# MachSacXa.net
KiCad netlist of a schematic drawn in Altium Designer
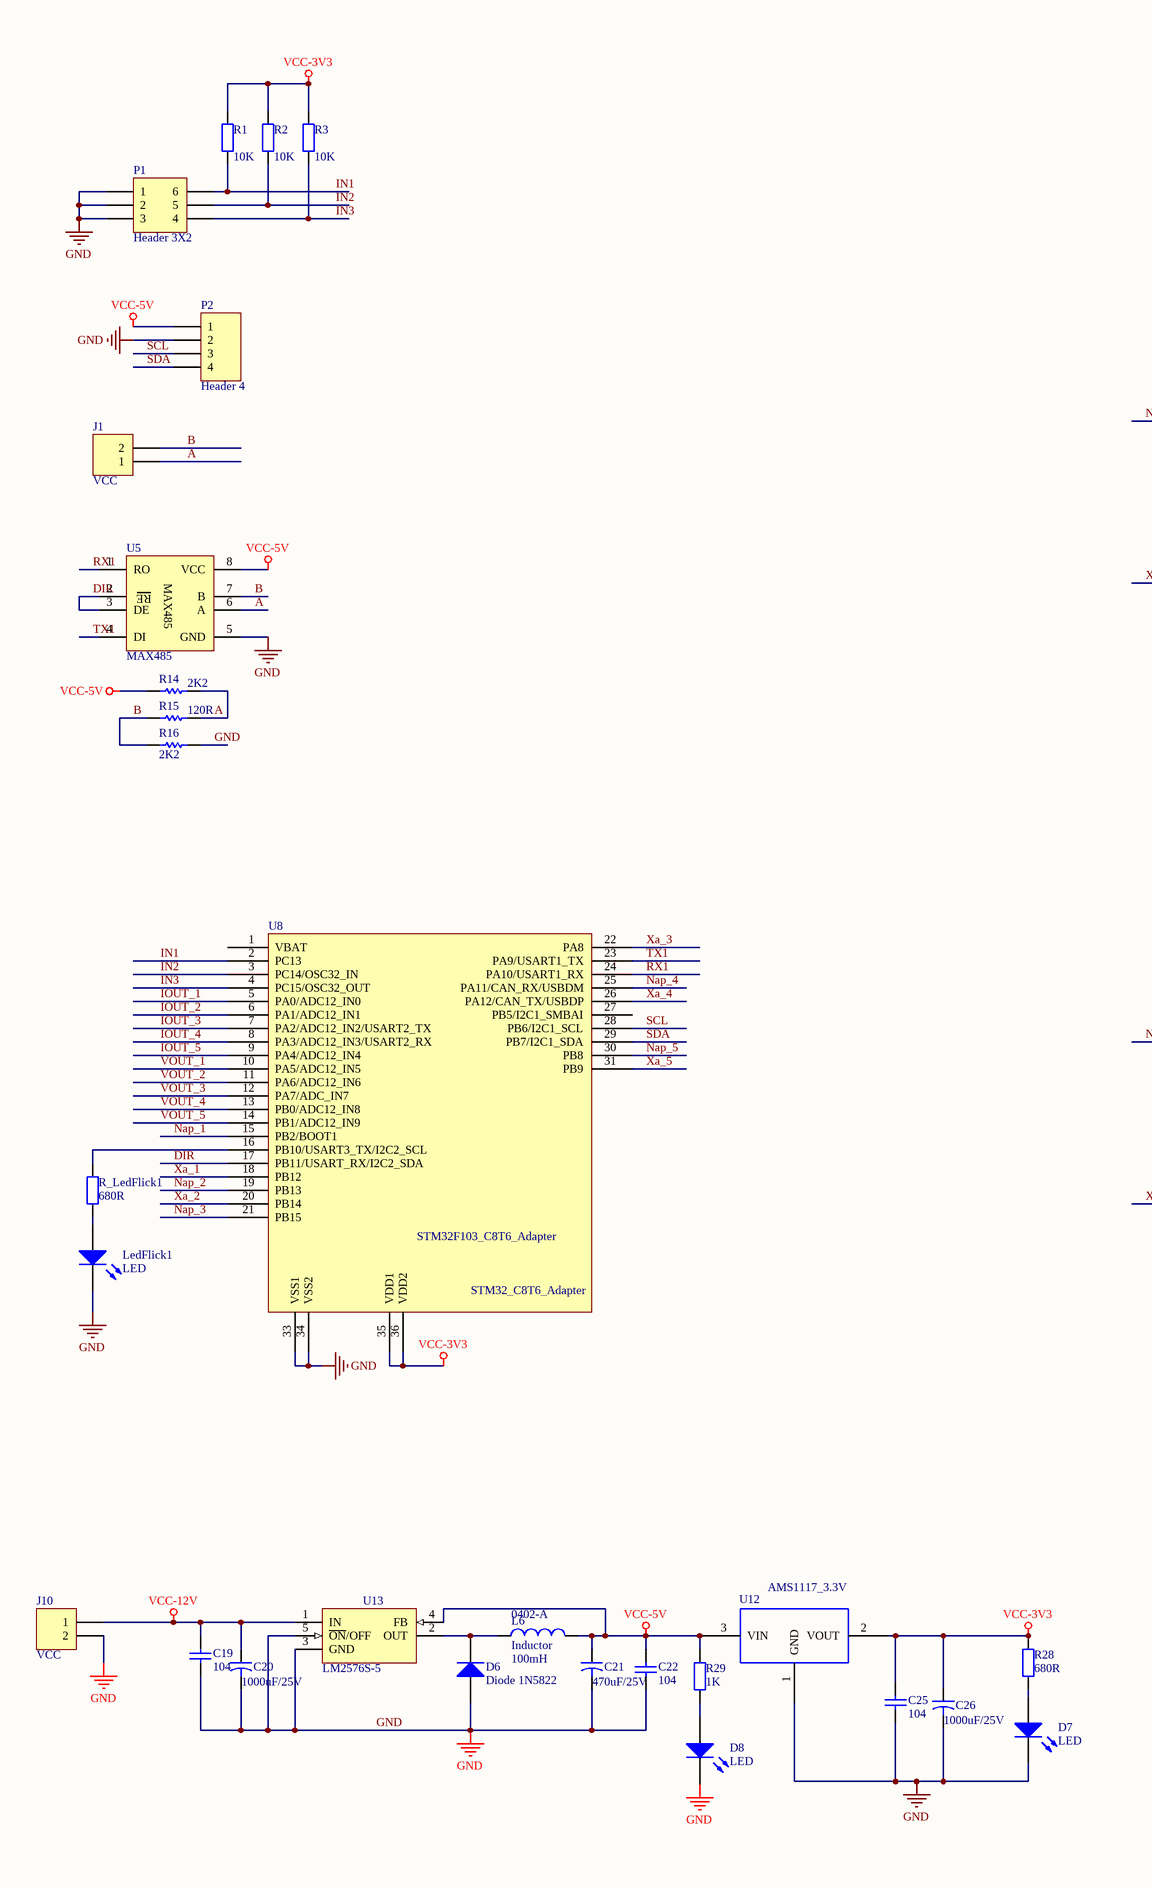
[diagram p0: MachSacXa.SchDoc, left]
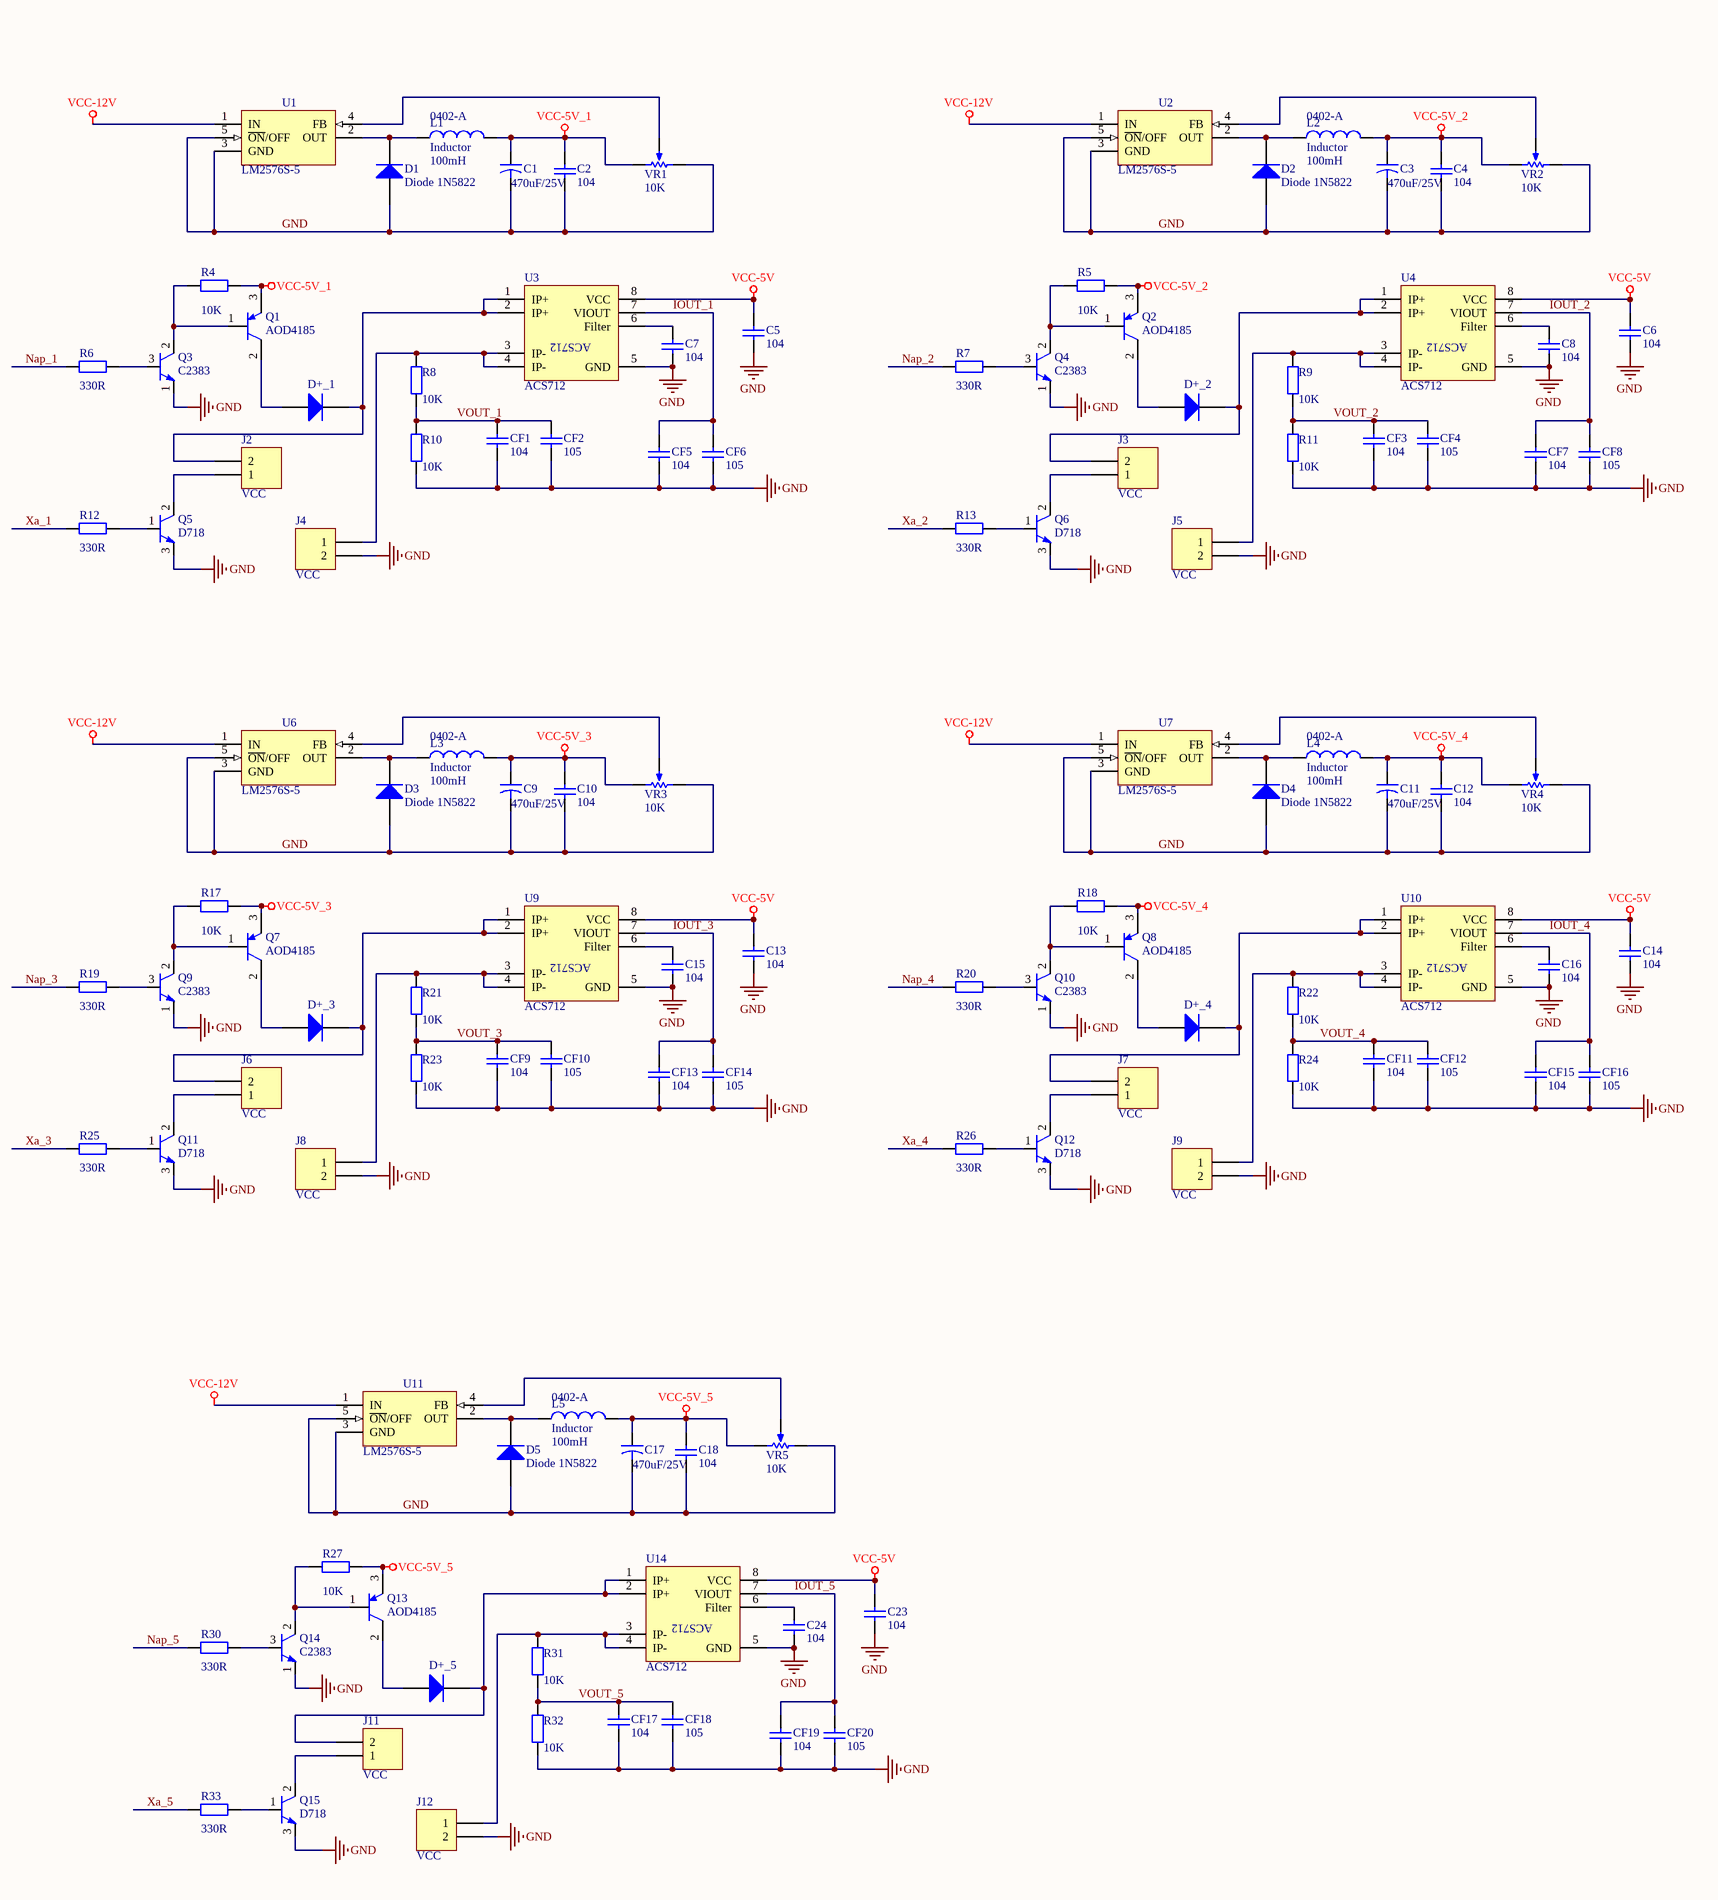
[diagram p1: MachSacXa.SchDoc, right]

(export (version "E")
  (design (tool "Eeschema 10.0.6"))
  (components
    (comp (ref "C1")
      (value "470uF/25V")
      (footprint "C_D300")
      (description "Capacitor")
      (fields (field (name "PUBLISHER") "Altium Limited"))
      (libsource (lib "Miscellaneous Devices") (part "Cap2"))
    )
    (comp (ref "C2")
      (value "104")
      (footprint "IC_dan:R/C_0805")
      (description "Capacitor")
      (fields (field (name "PUBLISHER") "Altium Limited"))
      (libsource (lib "Miscellaneous Devices") (part "Cap"))
    )
    (comp (ref "C3")
      (value "470uF/25V")
      (footprint "C_D300")
      (description "Capacitor")
      (fields (field (name "PUBLISHER") "Altium Limited"))
      (libsource (lib "Miscellaneous Devices") (part "Cap2"))
    )
    (comp (ref "C4")
      (value "104")
      (footprint "IC_dan:R/C_0805")
      (description "Capacitor")
      (fields (field (name "PUBLISHER") "Altium Limited"))
      (libsource (lib "Miscellaneous Devices") (part "Cap"))
    )
    (comp (ref "C5")
      (value "104")
      (footprint "IC_dan:R/C_0805")
      (description "Capacitor")
      (fields (field (name "PUBLISHER") "Altium Limited"))
      (libsource (lib "Miscellaneous Devices") (part "Cap"))
    )
    (comp (ref "C6")
      (value "104")
      (footprint "IC_dan:R/C_0805")
      (description "Capacitor")
      (fields (field (name "PUBLISHER") "Altium Limited"))
      (libsource (lib "Miscellaneous Devices") (part "Cap"))
    )
    (comp (ref "C7")
      (value "104")
      (footprint "IC_dan:R/C_0805")
      (description "Capacitor")
      (fields (field (name "PUBLISHER") "Altium Limited"))
      (libsource (lib "Miscellaneous Devices") (part "Cap"))
    )
    (comp (ref "C8")
      (value "104")
      (footprint "IC_dan:R/C_0805")
      (description "Capacitor")
      (fields (field (name "PUBLISHER") "Altium Limited"))
      (libsource (lib "Miscellaneous Devices") (part "Cap"))
    )
    (comp (ref "C9")
      (value "470uF/25V")
      (footprint "C_D300")
      (description "Capacitor")
      (fields (field (name "PUBLISHER") "Altium Limited"))
      (libsource (lib "Miscellaneous Devices") (part "Cap2"))
    )
    (comp (ref "C10")
      (value "104")
      (footprint "IC_dan:R/C_0805")
      (description "Capacitor")
      (fields (field (name "PUBLISHER") "Altium Limited"))
      (libsource (lib "Miscellaneous Devices") (part "Cap"))
    )
    (comp (ref "C11")
      (value "470uF/25V")
      (footprint "C_D300")
      (description "Capacitor")
      (fields (field (name "PUBLISHER") "Altium Limited"))
      (libsource (lib "Miscellaneous Devices") (part "Cap2"))
    )
    (comp (ref "C12")
      (value "104")
      (footprint "IC_dan:R/C_0805")
      (description "Capacitor")
      (fields (field (name "PUBLISHER") "Altium Limited"))
      (libsource (lib "Miscellaneous Devices") (part "Cap"))
    )
    (comp (ref "C13")
      (value "104")
      (footprint "IC_dan:R/C_0805")
      (description "Capacitor")
      (fields (field (name "PUBLISHER") "Altium Limited"))
      (libsource (lib "Miscellaneous Devices") (part "Cap"))
    )
    (comp (ref "C14")
      (value "104")
      (footprint "IC_dan:R/C_0805")
      (description "Capacitor")
      (fields (field (name "PUBLISHER") "Altium Limited"))
      (libsource (lib "Miscellaneous Devices") (part "Cap"))
    )
    (comp (ref "C15")
      (value "104")
      (footprint "IC_dan:R/C_0805")
      (description "Capacitor")
      (fields (field (name "PUBLISHER") "Altium Limited"))
      (libsource (lib "Miscellaneous Devices") (part "Cap"))
    )
    (comp (ref "C16")
      (value "104")
      (footprint "IC_dan:R/C_0805")
      (description "Capacitor")
      (fields (field (name "PUBLISHER") "Altium Limited"))
      (libsource (lib "Miscellaneous Devices") (part "Cap"))
    )
    (comp (ref "C17")
      (value "470uF/25V")
      (footprint "C_D300")
      (description "Capacitor")
      (fields (field (name "PUBLISHER") "Altium Limited"))
      (libsource (lib "Miscellaneous Devices") (part "Cap2"))
    )
    (comp (ref "C18")
      (value "104")
      (footprint "IC_dan:R/C_0805")
      (description "Capacitor")
      (fields (field (name "PUBLISHER") "Altium Limited"))
      (libsource (lib "Miscellaneous Devices") (part "Cap"))
    )
    (comp (ref "C19")
      (value "104")
      (footprint "IC_dan:R/C_0805")
      (description "Capacitor")
      (fields (field (name "PUBLISHER") "Altium Limited"))
      (libsource (lib "Miscellaneous Devices") (part "Cap"))
    )
    (comp (ref "C20")
      (value "1000uF/25V")
      (footprint "C_D300")
      (description "Capacitor")
      (fields (field (name "PUBLISHER") "Altium Limited"))
      (libsource (lib "Miscellaneous Devices") (part "Cap2"))
    )
    (comp (ref "C21")
      (value "470uF/25V")
      (footprint "C_D300")
      (description "Capacitor")
      (fields (field (name "PUBLISHER") "Altium Limited"))
      (libsource (lib "Miscellaneous Devices") (part "Cap2"))
    )
    (comp (ref "C22")
      (value "104")
      (footprint "IC_dan:R/C_0805")
      (description "Capacitor")
      (fields (field (name "PUBLISHER") "Altium Limited"))
      (libsource (lib "Miscellaneous Devices") (part "Cap"))
    )
    (comp (ref "C23")
      (value "104")
      (footprint "IC_dan:R/C_0805")
      (description "Capacitor")
      (fields (field (name "PUBLISHER") "Altium Limited"))
      (libsource (lib "Miscellaneous Devices") (part "Cap"))
    )
    (comp (ref "C24")
      (value "104")
      (footprint "IC_dan:R/C_0805")
      (description "Capacitor")
      (fields (field (name "PUBLISHER") "Altium Limited"))
      (libsource (lib "Miscellaneous Devices") (part "Cap"))
    )
    (comp (ref "C25")
      (value "104")
      (footprint "IC_dan:R/C_0805")
      (description "Capacitor")
      (fields (field (name "PUBLISHER") "Altium Limited"))
      (libsource (lib "Miscellaneous Devices") (part "Cap"))
    )
    (comp (ref "C26")
      (value "1000uF/25V")
      (footprint "C_D300")
      (description "Capacitor")
      (fields (field (name "PUBLISHER") "Altium Limited"))
      (libsource (lib "Miscellaneous Devices") (part "Cap2"))
    )
    (comp (ref "CF1")
      (value "104")
      (footprint "IC_dan:R/C_0805")
      (description "Capacitor")
      (fields (field (name "PUBLISHER") "Altium Limited"))
      (libsource (lib "Miscellaneous Devices") (part "Cap"))
    )
    (comp (ref "CF2")
      (value "105")
      (footprint "IC_dan:R/C_0805")
      (description "Capacitor")
      (fields (field (name "PUBLISHER") "Altium Limited"))
      (libsource (lib "Miscellaneous Devices") (part "Cap"))
    )
    (comp (ref "CF3")
      (value "104")
      (footprint "IC_dan:R/C_0805")
      (description "Capacitor")
      (fields (field (name "PUBLISHER") "Altium Limited"))
      (libsource (lib "Miscellaneous Devices") (part "Cap"))
    )
    (comp (ref "CF4")
      (value "105")
      (footprint "IC_dan:R/C_0805")
      (description "Capacitor")
      (fields (field (name "PUBLISHER") "Altium Limited"))
      (libsource (lib "Miscellaneous Devices") (part "Cap"))
    )
    (comp (ref "CF5")
      (value "104")
      (footprint "IC_dan:R/C_0805")
      (description "Capacitor")
      (fields (field (name "PUBLISHER") "Altium Limited"))
      (libsource (lib "Miscellaneous Devices") (part "Cap"))
    )
    (comp (ref "CF6")
      (value "105")
      (footprint "IC_dan:R/C_0805")
      (description "Capacitor")
      (fields (field (name "PUBLISHER") "Altium Limited"))
      (libsource (lib "Miscellaneous Devices") (part "Cap"))
    )
    (comp (ref "CF7")
      (value "104")
      (footprint "IC_dan:R/C_0805")
      (description "Capacitor")
      (fields (field (name "PUBLISHER") "Altium Limited"))
      (libsource (lib "Miscellaneous Devices") (part "Cap"))
    )
    (comp (ref "CF8")
      (value "105")
      (footprint "IC_dan:R/C_0805")
      (description "Capacitor")
      (fields (field (name "PUBLISHER") "Altium Limited"))
      (libsource (lib "Miscellaneous Devices") (part "Cap"))
    )
    (comp (ref "CF9")
      (value "104")
      (footprint "IC_dan:R/C_0805")
      (description "Capacitor")
      (fields (field (name "PUBLISHER") "Altium Limited"))
      (libsource (lib "Miscellaneous Devices") (part "Cap"))
    )
    (comp (ref "CF10")
      (value "105")
      (footprint "IC_dan:R/C_0805")
      (description "Capacitor")
      (fields (field (name "PUBLISHER") "Altium Limited"))
      (libsource (lib "Miscellaneous Devices") (part "Cap"))
    )
    (comp (ref "CF11")
      (value "104")
      (footprint "IC_dan:R/C_0805")
      (description "Capacitor")
      (fields (field (name "PUBLISHER") "Altium Limited"))
      (libsource (lib "Miscellaneous Devices") (part "Cap"))
    )
    (comp (ref "CF12")
      (value "105")
      (footprint "IC_dan:R/C_0805")
      (description "Capacitor")
      (fields (field (name "PUBLISHER") "Altium Limited"))
      (libsource (lib "Miscellaneous Devices") (part "Cap"))
    )
    (comp (ref "CF13")
      (value "104")
      (footprint "IC_dan:R/C_0805")
      (description "Capacitor")
      (fields (field (name "PUBLISHER") "Altium Limited"))
      (libsource (lib "Miscellaneous Devices") (part "Cap"))
    )
    (comp (ref "CF14")
      (value "105")
      (footprint "IC_dan:R/C_0805")
      (description "Capacitor")
      (fields (field (name "PUBLISHER") "Altium Limited"))
      (libsource (lib "Miscellaneous Devices") (part "Cap"))
    )
    (comp (ref "CF15")
      (value "104")
      (footprint "IC_dan:R/C_0805")
      (description "Capacitor")
      (fields (field (name "PUBLISHER") "Altium Limited"))
      (libsource (lib "Miscellaneous Devices") (part "Cap"))
    )
    (comp (ref "CF16")
      (value "105")
      (footprint "IC_dan:R/C_0805")
      (description "Capacitor")
      (fields (field (name "PUBLISHER") "Altium Limited"))
      (libsource (lib "Miscellaneous Devices") (part "Cap"))
    )
    (comp (ref "CF17")
      (value "104")
      (footprint "IC_dan:R/C_0805")
      (description "Capacitor")
      (fields (field (name "PUBLISHER") "Altium Limited"))
      (libsource (lib "Miscellaneous Devices") (part "Cap"))
    )
    (comp (ref "CF18")
      (value "105")
      (footprint "IC_dan:R/C_0805")
      (description "Capacitor")
      (fields (field (name "PUBLISHER") "Altium Limited"))
      (libsource (lib "Miscellaneous Devices") (part "Cap"))
    )
    (comp (ref "CF19")
      (value "104")
      (footprint "IC_dan:R/C_0805")
      (description "Capacitor")
      (fields (field (name "PUBLISHER") "Altium Limited"))
      (libsource (lib "Miscellaneous Devices") (part "Cap"))
    )
    (comp (ref "CF20")
      (value "105")
      (footprint "IC_dan:R/C_0805")
      (description "Capacitor")
      (fields (field (name "PUBLISHER") "Altium Limited"))
      (libsource (lib "Miscellaneous Devices") (part "Cap"))
    )
    (comp (ref "D+_1")
      (value "Diode 1N5822")
      (footprint "Diode_1A")
      (description "1 Amp General Purpose Rectifier")
      (fields (field (name "PUBLISHER") "Altium Limited"))
      (libsource (lib "Miscellaneous Devices") (part "Diode 1N4004"))
    )
    (comp (ref "D+_2")
      (value "Diode 1N5822")
      (footprint "Diode_1A")
      (description "1 Amp General Purpose Rectifier")
      (fields (field (name "PUBLISHER") "Altium Limited"))
      (libsource (lib "Miscellaneous Devices") (part "Diode 1N4004"))
    )
    (comp (ref "D+_3")
      (value "Diode 1N5822")
      (footprint "Diode_1A")
      (description "1 Amp General Purpose Rectifier")
      (fields (field (name "PUBLISHER") "Altium Limited"))
      (libsource (lib "Miscellaneous Devices") (part "Diode 1N4004"))
    )
    (comp (ref "D+_4")
      (value "Diode 1N5822")
      (footprint "Diode_1A")
      (description "1 Amp General Purpose Rectifier")
      (fields (field (name "PUBLISHER") "Altium Limited"))
      (libsource (lib "Miscellaneous Devices") (part "Diode 1N4004"))
    )
    (comp (ref "D+_5")
      (value "Diode 1N5822")
      (footprint "Diode_1A")
      (description "1 Amp General Purpose Rectifier")
      (fields (field (name "PUBLISHER") "Altium Limited"))
      (libsource (lib "Miscellaneous Devices") (part "Diode 1N4004"))
    )
    (comp (ref "D1")
      (value "Diode 1N5822")
      (footprint "Diode_1A")
      (description "1 Amp General Purpose Rectifier")
      (fields (field (name "PUBLISHER") "Altium Limited"))
      (libsource (lib "Miscellaneous Devices") (part "Diode 1N4004"))
    )
    (comp (ref "D2")
      (value "Diode 1N5822")
      (footprint "Diode_1A")
      (description "1 Amp General Purpose Rectifier")
      (fields (field (name "PUBLISHER") "Altium Limited"))
      (libsource (lib "Miscellaneous Devices") (part "Diode 1N4004"))
    )
    (comp (ref "D3")
      (value "Diode 1N5822")
      (footprint "Diode_1A")
      (description "1 Amp General Purpose Rectifier")
      (fields (field (name "PUBLISHER") "Altium Limited"))
      (libsource (lib "Miscellaneous Devices") (part "Diode 1N4004"))
    )
    (comp (ref "D4")
      (value "Diode 1N5822")
      (footprint "Diode_1A")
      (description "1 Amp General Purpose Rectifier")
      (fields (field (name "PUBLISHER") "Altium Limited"))
      (libsource (lib "Miscellaneous Devices") (part "Diode 1N4004"))
    )
    (comp (ref "D5")
      (value "Diode 1N5822")
      (footprint "Diode_1A")
      (description "1 Amp General Purpose Rectifier")
      (fields (field (name "PUBLISHER") "Altium Limited"))
      (libsource (lib "Miscellaneous Devices") (part "Diode 1N4004"))
    )
    (comp (ref "D6")
      (value "Diode 1N5822")
      (footprint "Diode_1A")
      (description "1 Amp General Purpose Rectifier")
      (fields (field (name "PUBLISHER") "Altium Limited"))
      (libsource (lib "Miscellaneous Devices") (part "Diode 1N4004"))
    )
    (comp (ref "D7")
      (value "LED")
      (footprint "IC_dan:LED_SMD (0805)")
      (description "Typical INFRARED GaAs LED")
      (fields (field (name "PUBLISHER") "Altium Limited"))
      (libsource (lib "Miscellaneous Devices") (part "LED0"))
    )
    (comp (ref "D8")
      (value "LED")
      (footprint "LED_SMD (0805)")
      (description "Typical INFRARED GaAs LED")
      (fields (field (name "PUBLISHER") "Altium Limited"))
      (libsource (lib "Miscellaneous Devices") (part "LED0"))
    )
    (comp (ref "J1")
      (value "VCC")
      (footprint "HEADER1_2(400)")
      (description "Header, 2-Pin")
      (fields (field (name "PUBLISHER") "Altium Limited"))
      (libsource (lib "") (part "Header 2_2"))
    )
    (comp (ref "J2")
      (value "VCC")
      (footprint "HEADER1_2(400)")
      (description "Header, 2-Pin")
      (fields (field (name "PUBLISHER") "Altium Limited"))
      (libsource (lib "") (part "Header 2_1"))
    )
    (comp (ref "J3")
      (value "VCC")
      (footprint "HEADER1_2(400)")
      (description "Header, 2-Pin")
      (fields (field (name "PUBLISHER") "Altium Limited"))
      (libsource (lib "") (part "Header 2_1"))
    )
    (comp (ref "J4")
      (value "VCC")
      (footprint "HEADER1_2(400)")
      (description "Header, 2-Pin")
      (fields (field (name "PUBLISHER") "Altium Limited"))
      (libsource (lib "Miscellaneous Connectors") (part "Header 2"))
    )
    (comp (ref "J5")
      (value "VCC")
      (footprint "HEADER1_2(400)")
      (description "Header, 2-Pin")
      (fields (field (name "PUBLISHER") "Altium Limited"))
      (libsource (lib "Miscellaneous Connectors") (part "Header 2"))
    )
    (comp (ref "J6")
      (value "VCC")
      (footprint "HEADER1_2(400)")
      (description "Header, 2-Pin")
      (fields (field (name "PUBLISHER") "Altium Limited"))
      (libsource (lib "") (part "Header 2_1"))
    )
    (comp (ref "J7")
      (value "VCC")
      (footprint "HEADER1_2(400)")
      (description "Header, 2-Pin")
      (fields (field (name "PUBLISHER") "Altium Limited"))
      (libsource (lib "") (part "Header 2_1"))
    )
    (comp (ref "J8")
      (value "VCC")
      (footprint "HEADER1_2(400)")
      (description "Header, 2-Pin")
      (fields (field (name "PUBLISHER") "Altium Limited"))
      (libsource (lib "Miscellaneous Connectors") (part "Header 2"))
    )
    (comp (ref "J9")
      (value "VCC")
      (footprint "HEADER1_2(400)")
      (description "Header, 2-Pin")
      (fields (field (name "PUBLISHER") "Altium Limited"))
      (libsource (lib "Miscellaneous Connectors") (part "Header 2"))
    )
    (comp (ref "J10")
      (value "VCC")
      (footprint "HEADER1_2(400)")
      (description "Header, 2-Pin")
      (fields (field (name "PUBLISHER") "Altium Limited"))
      (libsource (lib "Miscellaneous Connectors") (part "Header 2"))
    )
    (comp (ref "J11")
      (value "VCC")
      (footprint "HEADER1_2(400)")
      (description "Header, 2-Pin")
      (fields (field (name "PUBLISHER") "Altium Limited"))
      (libsource (lib "") (part "Header 2_1"))
    )
    (comp (ref "J12")
      (value "VCC")
      (footprint "HEADER1_2(400)")
      (description "Header, 2-Pin")
      (fields (field (name "PUBLISHER") "Altium Limited"))
      (libsource (lib "Miscellaneous Connectors") (part "Header 2"))
    )
    (comp (ref "L1")
      (value "Inductor")
      (footprint "Cuon_cam(100mH)")
      (fields
        (field (name "PACKAGEREFERENCE") "0402-A")
        (field (name "ALTIUM_VALUE") "100mH")
        (field (name "PUBLISHER") "Altium Limited")
      )
      (libsource (lib "Miscellaneous Devices") (part "Inductor"))
    )
    (comp (ref "L2")
      (value "Inductor")
      (footprint "Cuon_cam(100mH)")
      (fields
        (field (name "PACKAGEREFERENCE") "0402-A")
        (field (name "ALTIUM_VALUE") "100mH")
        (field (name "PUBLISHER") "Altium Limited")
      )
      (libsource (lib "Miscellaneous Devices") (part "Inductor"))
    )
    (comp (ref "L3")
      (value "Inductor")
      (footprint "Cuon_cam(100mH)")
      (fields
        (field (name "PACKAGEREFERENCE") "0402-A")
        (field (name "ALTIUM_VALUE") "100mH")
        (field (name "PUBLISHER") "Altium Limited")
      )
      (libsource (lib "Miscellaneous Devices") (part "Inductor"))
    )
    (comp (ref "L4")
      (value "Inductor")
      (footprint "Cuon_cam(100mH)")
      (fields
        (field (name "PACKAGEREFERENCE") "0402-A")
        (field (name "ALTIUM_VALUE") "100mH")
        (field (name "PUBLISHER") "Altium Limited")
      )
      (libsource (lib "Miscellaneous Devices") (part "Inductor"))
    )
    (comp (ref "L5")
      (value "Inductor")
      (footprint "Cuon_cam(100mH)")
      (fields
        (field (name "PACKAGEREFERENCE") "0402-A")
        (field (name "ALTIUM_VALUE") "100mH")
        (field (name "PUBLISHER") "Altium Limited")
      )
      (libsource (lib "Miscellaneous Devices") (part "Inductor"))
    )
    (comp (ref "L6")
      (value "Inductor")
      (footprint "Cuon_cam(100mH)")
      (fields
        (field (name "PACKAGEREFERENCE") "0402-A")
        (field (name "ALTIUM_VALUE") "100mH")
        (field (name "PUBLISHER") "Altium Limited")
      )
      (libsource (lib "Miscellaneous Devices") (part "Inductor"))
    )
    (comp (ref "LedFlick1")
      (value "LED")
      (footprint "IC_dan:LED_SMD (0805)")
      (description "Typical INFRARED GaAs LED")
      (fields (field (name "PUBLISHER") "Altium Limited"))
      (libsource (lib "Miscellaneous Devices") (part "LED0"))
    )
    (comp (ref "P1")
      (value "Header 3X2")
      (footprint "DIP6_300")
      (description "Header, 3-Pin, Dual row")
      (fields (field (name "PUBLISHER") "Altium Limited"))
      (libsource (lib "Connectors") (part "Header 3X2"))
    )
    (comp (ref "P2")
      (value "Header 4")
      (footprint "CON-Trang1_4")
      (description "Header, 4-Pin")
      (fields (field (name "PUBLISHER") "Altium Limited"))
      (libsource (lib "Connectors") (part "Header 4"))
    )
    (comp (ref "Q1")
      (value "AOD4185")
      (footprint "AOD4185")
      (fields (field (name "Comment") "NPN_ECB"))
      (libsource (lib "DEVICE") (part "TR_PNP_ECB"))
    )
    (comp (ref "Q2")
      (value "AOD4185")
      (footprint "AOD4185")
      (fields (field (name "Comment") "NPN_ECB"))
      (libsource (lib "DEVICE") (part "TR_PNP_ECB"))
    )
    (comp (ref "Q3")
      (value "C2383")
      (footprint "C1815/C945")
      (fields (field (name "Comment") "TR_NPN_ECB"))
      (libsource (lib "DEVICE") (part "TR_NPN_ECB"))
    )
    (comp (ref "Q4")
      (value "C2383")
      (footprint "C1815/C945")
      (fields (field (name "Comment") "TR_NPN_ECB"))
      (libsource (lib "DEVICE") (part "TR_NPN_ECB"))
    )
    (comp (ref "Q5")
      (value "D718")
      (footprint "D718")
      (fields (field (name "Comment") "TR_NPN_D718"))
      (libsource (lib "DEVICE") (part "TR_NPN_D718"))
    )
    (comp (ref "Q6")
      (value "D718")
      (footprint "D718")
      (fields (field (name "Comment") "TR_NPN_D718"))
      (libsource (lib "DEVICE") (part "TR_NPN_D718"))
    )
    (comp (ref "Q7")
      (value "AOD4185")
      (footprint "AOD4185")
      (fields (field (name "Comment") "NPN_ECB"))
      (libsource (lib "DEVICE") (part "TR_PNP_ECB"))
    )
    (comp (ref "Q8")
      (value "AOD4185")
      (footprint "AOD4185")
      (fields (field (name "Comment") "NPN_ECB"))
      (libsource (lib "DEVICE") (part "TR_PNP_ECB"))
    )
    (comp (ref "Q9")
      (value "C2383")
      (footprint "C1815/C945")
      (fields (field (name "Comment") "TR_NPN_ECB"))
      (libsource (lib "DEVICE") (part "TR_NPN_ECB"))
    )
    (comp (ref "Q10")
      (value "C2383")
      (footprint "C1815/C945")
      (fields (field (name "Comment") "TR_NPN_ECB"))
      (libsource (lib "DEVICE") (part "TR_NPN_ECB"))
    )
    (comp (ref "Q11")
      (value "D718")
      (footprint "D718")
      (fields (field (name "Comment") "TR_NPN_D718"))
      (libsource (lib "DEVICE") (part "TR_NPN_D718"))
    )
    (comp (ref "Q12")
      (value "D718")
      (footprint "D718")
      (fields (field (name "Comment") "TR_NPN_D718"))
      (libsource (lib "DEVICE") (part "TR_NPN_D718"))
    )
    (comp (ref "Q13")
      (value "AOD4185")
      (footprint "AOD4185")
      (fields (field (name "Comment") "NPN_ECB"))
      (libsource (lib "DEVICE") (part "TR_PNP_ECB"))
    )
    (comp (ref "Q14")
      (value "C2383")
      (footprint "C1815/C945")
      (fields (field (name "Comment") "TR_NPN_ECB"))
      (libsource (lib "DEVICE") (part "TR_NPN_ECB"))
    )
    (comp (ref "Q15")
      (value "D718")
      (footprint "D718")
      (fields (field (name "Comment") "TR_NPN_D718"))
      (libsource (lib "DEVICE") (part "TR_NPN_D718"))
    )
    (comp (ref "R1")
      (value "10K")
      (footprint "R/C_0805")
      (description "Resistor")
      (fields (field (name "PUBLISHER") "Altium Limited"))
      (libsource (lib "") (part "Res2_2"))
    )
    (comp (ref "R2")
      (value "10K")
      (footprint "R/C_0805")
      (description "Resistor")
      (fields (field (name "PUBLISHER") "Altium Limited"))
      (libsource (lib "") (part "Res2_2"))
    )
    (comp (ref "R3")
      (value "10K")
      (footprint "R/C_0805")
      (description "Resistor")
      (fields (field (name "PUBLISHER") "Altium Limited"))
      (libsource (lib "") (part "Res2_2"))
    )
    (comp (ref "R4")
      (value "10K")
      (footprint "R/C_0805")
      (description "Resistor")
      (fields (field (name "PUBLISHER") "Altium Limited"))
      (libsource (lib "") (part "Res2_1"))
    )
    (comp (ref "R5")
      (value "10K")
      (footprint "R/C_0805")
      (description "Resistor")
      (fields (field (name "PUBLISHER") "Altium Limited"))
      (libsource (lib "") (part "Res2_1"))
    )
    (comp (ref "R6")
      (value "330R")
      (footprint "R/C_0805")
      (description "Resistor")
      (fields (field (name "PUBLISHER") "Altium Limited"))
      (libsource (lib "Miscellaneous Devices") (part "Res2"))
    )
    (comp (ref "R7")
      (value "330R")
      (footprint "R/C_0805")
      (description "Resistor")
      (fields (field (name "PUBLISHER") "Altium Limited"))
      (libsource (lib "Miscellaneous Devices") (part "Res2"))
    )
    (comp (ref "R8")
      (value "10K")
      (footprint "R/C_0805")
      (description "Resistor")
      (fields (field (name "PUBLISHER") "Altium Limited"))
      (libsource (lib "") (part "Res2_2"))
    )
    (comp (ref "R9")
      (value "10K")
      (footprint "R/C_0805")
      (description "Resistor")
      (fields (field (name "PUBLISHER") "Altium Limited"))
      (libsource (lib "") (part "Res2_2"))
    )
    (comp (ref "R10")
      (value "10K")
      (footprint "R/C_0805")
      (description "Resistor")
      (fields (field (name "PUBLISHER") "Altium Limited"))
      (libsource (lib "") (part "Res2_2"))
    )
    (comp (ref "R11")
      (value "10K")
      (footprint "R/C_0805")
      (description "Resistor")
      (fields (field (name "PUBLISHER") "Altium Limited"))
      (libsource (lib "") (part "Res2_2"))
    )
    (comp (ref "R12")
      (value "330R")
      (footprint "R/C_0805")
      (description "Resistor")
      (fields (field (name "PUBLISHER") "Altium Limited"))
      (libsource (lib "Miscellaneous Devices") (part "Res2"))
    )
    (comp (ref "R13")
      (value "330R")
      (footprint "R/C_0805")
      (description "Resistor")
      (fields (field (name "PUBLISHER") "Altium Limited"))
      (libsource (lib "Miscellaneous Devices") (part "Res2"))
    )
    (comp (ref "R14")
      (value "2K2")
      (footprint "R/C_0805")
      (description "Resistor")
      (fields (field (name "Comment") "Res1") (field (name "PUBLISHER") "Altium Limited"))
      (libsource (lib "Miscellaneous Devices") (part "Res1"))
    )
    (comp (ref "R15")
      (value "120R")
      (footprint "R/C_0805")
      (description "Resistor")
      (fields (field (name "Comment") "Res1") (field (name "PUBLISHER") "Altium Limited"))
      (libsource (lib "Miscellaneous Devices") (part "Res1"))
    )
    (comp (ref "R16")
      (value "2K2")
      (footprint "R/C_0805")
      (description "Resistor")
      (fields (field (name "Comment") "Res1") (field (name "PUBLISHER") "Altium Limited"))
      (libsource (lib "Miscellaneous Devices") (part "Res1"))
    )
    (comp (ref "R17")
      (value "10K")
      (footprint "R/C_0805")
      (description "Resistor")
      (fields (field (name "PUBLISHER") "Altium Limited"))
      (libsource (lib "") (part "Res2_1"))
    )
    (comp (ref "R18")
      (value "10K")
      (footprint "R/C_0805")
      (description "Resistor")
      (fields (field (name "PUBLISHER") "Altium Limited"))
      (libsource (lib "") (part "Res2_1"))
    )
    (comp (ref "R19")
      (value "330R")
      (footprint "R/C_0805")
      (description "Resistor")
      (fields (field (name "PUBLISHER") "Altium Limited"))
      (libsource (lib "Miscellaneous Devices") (part "Res2"))
    )
    (comp (ref "R20")
      (value "330R")
      (footprint "R/C_0805")
      (description "Resistor")
      (fields (field (name "PUBLISHER") "Altium Limited"))
      (libsource (lib "Miscellaneous Devices") (part "Res2"))
    )
    (comp (ref "R21")
      (value "10K")
      (footprint "R/C_0805")
      (description "Resistor")
      (fields (field (name "PUBLISHER") "Altium Limited"))
      (libsource (lib "") (part "Res2_2"))
    )
    (comp (ref "R22")
      (value "10K")
      (footprint "R/C_0805")
      (description "Resistor")
      (fields (field (name "PUBLISHER") "Altium Limited"))
      (libsource (lib "") (part "Res2_2"))
    )
    (comp (ref "R23")
      (value "10K")
      (footprint "R/C_0805")
      (description "Resistor")
      (fields (field (name "PUBLISHER") "Altium Limited"))
      (libsource (lib "") (part "Res2_2"))
    )
    (comp (ref "R24")
      (value "10K")
      (footprint "R/C_0805")
      (description "Resistor")
      (fields (field (name "PUBLISHER") "Altium Limited"))
      (libsource (lib "") (part "Res2_2"))
    )
    (comp (ref "R25")
      (value "330R")
      (footprint "R/C_0805")
      (description "Resistor")
      (fields (field (name "PUBLISHER") "Altium Limited"))
      (libsource (lib "Miscellaneous Devices") (part "Res2"))
    )
    (comp (ref "R26")
      (value "330R")
      (footprint "R/C_0805")
      (description "Resistor")
      (fields (field (name "PUBLISHER") "Altium Limited"))
      (libsource (lib "Miscellaneous Devices") (part "Res2"))
    )
    (comp (ref "R27")
      (value "10K")
      (footprint "R/C_0805")
      (description "Resistor")
      (fields (field (name "PUBLISHER") "Altium Limited"))
      (libsource (lib "") (part "Res2_1"))
    )
    (comp (ref "R28")
      (value "680R")
      (footprint "R/C_0805")
      (description "Resistor")
      (fields (field (name "PUBLISHER") "Altium Limited"))
      (libsource (lib "") (part "Res2_3"))
    )
    (comp (ref "R29")
      (value "1K")
      (footprint "R/C_0805")
      (description "Resistor")
      (fields (field (name "PUBLISHER") "Altium Limited"))
      (libsource (lib "") (part "Res2_3"))
    )
    (comp (ref "R30")
      (value "330R")
      (footprint "R/C_0805")
      (description "Resistor")
      (fields (field (name "PUBLISHER") "Altium Limited"))
      (libsource (lib "Miscellaneous Devices") (part "Res2"))
    )
    (comp (ref "R31")
      (value "10K")
      (footprint "R/C_0805")
      (description "Resistor")
      (fields (field (name "PUBLISHER") "Altium Limited"))
      (libsource (lib "") (part "Res2_2"))
    )
    (comp (ref "R32")
      (value "10K")
      (footprint "R/C_0805")
      (description "Resistor")
      (fields (field (name "PUBLISHER") "Altium Limited"))
      (libsource (lib "") (part "Res2_2"))
    )
    (comp (ref "R33")
      (value "330R")
      (footprint "R/C_0805")
      (description "Resistor")
      (fields (field (name "PUBLISHER") "Altium Limited"))
      (libsource (lib "Miscellaneous Devices") (part "Res2"))
    )
    (comp (ref "R_LedFlick1")
      (value "680R")
      (footprint "R/C_0805")
      (description "Resistor")
      (fields (field (name "PUBLISHER") "Altium Limited"))
      (libsource (lib "") (part "Res2_3"))
    )
    (comp (ref "U1")
      (value "LM2576S-5")
      (footprint "THROUGH HOLES:LM2576(1)")
      (description "Simple Switcher 3A Step Down Voltage Regulator")
      (fields (field (name "PUBLISHER") "Altium Limited"))
      (libsource (lib "NSC Power Mgt Switching Regulator") (part "LM2576S-5.0"))
    )
    (comp (ref "U2")
      (value "LM2576S-5")
      (footprint "THROUGH HOLES:LM2576(1)")
      (description "Simple Switcher 3A Step Down Voltage Regulator")
      (fields (field (name "PUBLISHER") "Altium Limited"))
      (libsource (lib "NSC Power Mgt Switching Regulator") (part "LM2576S-5.0"))
    )
    (comp (ref "U3") (value "ACS712") (footprint "DS1307") (libsource (lib "DEVICE") (part "ACS712")))
    (comp (ref "U4") (value "ACS712") (footprint "DS1307") (libsource (lib "DEVICE") (part "ACS712")))
    (comp (ref "U5") (value "MAX485") (footprint "DIP8_300") (libsource (lib "DEVICE") (part "MAX485")))
    (comp (ref "U6")
      (value "LM2576S-5")
      (footprint "THROUGH HOLES:LM2576(1)")
      (description "Simple Switcher 3A Step Down Voltage Regulator")
      (fields (field (name "PUBLISHER") "Altium Limited"))
      (libsource (lib "NSC Power Mgt Switching Regulator") (part "LM2576S-5.0"))
    )
    (comp (ref "U7")
      (value "LM2576S-5")
      (footprint "THROUGH HOLES:LM2576(1)")
      (description "Simple Switcher 3A Step Down Voltage Regulator")
      (fields (field (name "PUBLISHER") "Altium Limited"))
      (libsource (lib "NSC Power Mgt Switching Regulator") (part "LM2576S-5.0"))
    )
    (comp (ref "U8")
      (value "STM32F103_C8T6_Adapter")
      (footprint "Dip36(9x4)")
      (libsource (lib "DEVICE") (part "STM32_C8T6_Adapter"))
    )
    (comp (ref "U9") (value "ACS712") (footprint "DS1307") (libsource (lib "DEVICE") (part "ACS712")))
    (comp (ref "U10") (value "ACS712") (footprint "DS1307") (libsource (lib "DEVICE") (part "ACS712")))
    (comp (ref "U11")
      (value "LM2576S-5")
      (footprint "THROUGH HOLES:LM2576(1)")
      (description "Simple Switcher 3A Step Down Voltage Regulator")
      (fields (field (name "PUBLISHER") "Altium Limited"))
      (libsource (lib "NSC Power Mgt Switching Regulator") (part "LM2576S-5.0"))
    )
    (comp (ref "U12")
      (value "AMS1117_3.3V")
      (footprint "AMS1117_(SOT_223)")
      (libsource (lib "DEVICE") (part "AMS1117_3.3V"))
    )
    (comp (ref "U13")
      (value "LM2576S-5")
      (footprint "LM2576")
      (description "Simple Switcher 3A Step Down Voltage Regulator")
      (fields (field (name "PUBLISHER") "Altium Limited"))
      (libsource (lib "NSC Power Mgt Switching Regulator") (part "LM2576S-5.0"))
    )
    (comp (ref "U14") (value "ACS712") (footprint "DS1307") (libsource (lib "DEVICE") (part "ACS712")))
    (comp (ref "VR1")
      (value "10K")
      (footprint "VR_3")
      (fields (field (name "Comment") "Bien tro"))
      (libsource (lib "DEVICE") (part "VR"))
    )
    (comp (ref "VR2")
      (value "10K")
      (footprint "VR_3")
      (fields (field (name "Comment") "Bien tro"))
      (libsource (lib "DEVICE") (part "VR"))
    )
    (comp (ref "VR3")
      (value "10K")
      (footprint "VR_3")
      (fields (field (name "Comment") "Bien tro"))
      (libsource (lib "DEVICE") (part "VR"))
    )
    (comp (ref "VR4")
      (value "10K")
      (footprint "VR_3")
      (fields (field (name "Comment") "Bien tro"))
      (libsource (lib "DEVICE") (part "VR"))
    )
    (comp (ref "VR5")
      (value "10K")
      (footprint "VR_3")
      (fields (field (name "Comment") "Bien tro"))
      (libsource (lib "DEVICE") (part "VR"))
    )
  )
  (nets
    (net (code "1") (name "/A") (class "Default")
      (node (ref "J1") (pin "1") (pinfunction "1_1") (pintype "passive"))
      (node (ref "R14") (pin "1") (pinfunction "1_1") (pintype "passive"))
      (node (ref "R15") (pin "1") (pinfunction "1_1") (pintype "passive"))
      (node (ref "U5") (pin "6") (pinfunction "A_6") (pintype "passive"))
    )
    (net (code "2") (name "/B") (class "Default")
      (node (ref "J1") (pin "2") (pinfunction "2_2") (pintype "passive"))
      (node (ref "R15") (pin "2") (pinfunction "2_2") (pintype "passive"))
      (node (ref "R16") (pin "2") (pinfunction "2_2") (pintype "passive"))
      (node (ref "U5") (pin "7") (pinfunction "B_7") (pintype "passive"))
    )
    (net (code "3") (name "/DIR") (class "Default")
      (node (ref "U5") (pin "2") (pinfunction "2_2") (pintype "passive"))
      (node (ref "U5") (pin "3") (pinfunction "DE_3") (pintype "passive"))
      (node (ref "U8") (pin "17") (pinfunction "PB11/USART_RX/I2C2_SDA_17") (pintype "passive"))
    )
    (net (code "4") (name "/IN1") (class "Default")
      (node (ref "P1") (pin "6") (pinfunction "6_6") (pintype "passive"))
      (node (ref "R1") (pin "1") (pinfunction "1_1") (pintype "passive"))
      (node (ref "U8") (pin "2") (pinfunction "PC13_2") (pintype "passive"))
    )
    (net (code "5") (name "/IN2") (class "Default")
      (node (ref "P1") (pin "5") (pinfunction "5_5") (pintype "passive"))
      (node (ref "R2") (pin "1") (pinfunction "1_1") (pintype "passive"))
      (node (ref "U8") (pin "3") (pinfunction "PC14/OSC32_IN_3") (pintype "passive"))
    )
    (net (code "6") (name "/IN3") (class "Default")
      (node (ref "P1") (pin "4") (pinfunction "4_4") (pintype "passive"))
      (node (ref "R3") (pin "1") (pinfunction "1_1") (pintype "passive"))
      (node (ref "U8") (pin "4") (pinfunction "PC15/OSC32_OUT_4") (pintype "passive"))
    )
    (net (code "7") (name "/IOUT_1") (class "Default")
      (node (ref "CF5") (pin "1") (pinfunction "1_1") (pintype "passive"))
      (node (ref "CF6") (pin "1") (pinfunction "1_1") (pintype "passive"))
      (node (ref "U3") (pin "7") (pinfunction "VIOUT_7") (pintype "passive"))
      (node (ref "U8") (pin "5") (pinfunction "PA0/ADC12_IN0_5") (pintype "passive"))
    )
    (net (code "8") (name "/IOUT_2") (class "Default")
      (node (ref "CF7") (pin "1") (pinfunction "1_1") (pintype "passive"))
      (node (ref "CF8") (pin "1") (pinfunction "1_1") (pintype "passive"))
      (node (ref "U4") (pin "7") (pinfunction "VIOUT_7") (pintype "passive"))
      (node (ref "U8") (pin "6") (pinfunction "PA1/ADC12_IN1_6") (pintype "passive"))
    )
    (net (code "9") (name "/IOUT_3") (class "Default")
      (node (ref "CF13") (pin "1") (pinfunction "1_1") (pintype "passive"))
      (node (ref "CF14") (pin "1") (pinfunction "1_1") (pintype "passive"))
      (node (ref "U8") (pin "7") (pinfunction "PA2/ADC12_IN2/USART2_TX_7") (pintype "passive"))
      (node (ref "U9") (pin "7") (pinfunction "VIOUT_7") (pintype "passive"))
    )
    (net (code "10") (name "/IOUT_4") (class "Default")
      (node (ref "CF15") (pin "1") (pinfunction "1_1") (pintype "passive"))
      (node (ref "CF16") (pin "1") (pinfunction "1_1") (pintype "passive"))
      (node (ref "U10") (pin "7") (pinfunction "VIOUT_7") (pintype "passive"))
      (node (ref "U8") (pin "8") (pinfunction "PA3/ADC12_IN3/USART2_RX_8") (pintype "passive"))
    )
    (net (code "11") (name "/IOUT_5") (class "Default")
      (node (ref "CF19") (pin "1") (pinfunction "1_1") (pintype "passive"))
      (node (ref "CF20") (pin "1") (pinfunction "1_1") (pintype "passive"))
      (node (ref "U14") (pin "7") (pinfunction "VIOUT_7") (pintype "passive"))
      (node (ref "U8") (pin "9") (pinfunction "PA4/ADC12_IN4_9") (pintype "passive"))
    )
    (net (code "12") (name "/Nap_1") (class "Default")
      (node (ref "R6") (pin "1") (pinfunction "1_1") (pintype "passive"))
      (node (ref "U8") (pin "15") (pinfunction "PB2/BOOT1_15") (pintype "passive"))
    )
    (net (code "13") (name "/Nap_2") (class "Default")
      (node (ref "R7") (pin "1") (pinfunction "1_1") (pintype "passive"))
      (node (ref "U8") (pin "19") (pinfunction "PB13_19") (pintype "passive"))
    )
    (net (code "14") (name "/Nap_3") (class "Default")
      (node (ref "R19") (pin "1") (pinfunction "1_1") (pintype "passive"))
      (node (ref "U8") (pin "21") (pinfunction "PB15_21") (pintype "passive"))
    )
    (net (code "15") (name "/Nap_4") (class "Default")
      (node (ref "R20") (pin "1") (pinfunction "1_1") (pintype "passive"))
      (node (ref "U8") (pin "25") (pinfunction "PA11/CAN_RX/USBDM_25") (pintype "passive"))
    )
    (net (code "16") (name "/Nap_5") (class "Default")
      (node (ref "R30") (pin "1") (pinfunction "1_1") (pintype "passive"))
      (node (ref "U8") (pin "30") (pinfunction "PB8_30") (pintype "passive"))
    )
    (net (code "17") (name "/RX1") (class "Default")
      (node (ref "U5") (pin "1") (pinfunction "RO_1") (pintype "passive"))
      (node (ref "U8") (pin "24") (pinfunction "PA10/USART1_RX_24") (pintype "passive"))
    )
    (net (code "18") (name "/SCL") (class "Default")
      (node (ref "P2") (pin "3") (pinfunction "3_3") (pintype "passive"))
      (node (ref "U8") (pin "28") (pinfunction "PB6/I2C1_SCL_28") (pintype "passive"))
    )
    (net (code "19") (name "/SDA") (class "Default")
      (node (ref "P2") (pin "4") (pinfunction "4_4") (pintype "passive"))
      (node (ref "U8") (pin "29") (pinfunction "PB7/I2C1_SDA_29") (pintype "passive"))
    )
    (net (code "20") (name "/TX1") (class "Default")
      (node (ref "U5") (pin "4") (pinfunction "DI_4") (pintype "passive"))
      (node (ref "U8") (pin "23") (pinfunction "PA9/USART1_TX_23") (pintype "passive"))
    )
    (net (code "21") (name "/VOUT_1") (class "Default")
      (node (ref "CF1") (pin "1") (pinfunction "1_1") (pintype "passive"))
      (node (ref "CF2") (pin "1") (pinfunction "1_1") (pintype "passive"))
      (node (ref "R10") (pin "2") (pinfunction "2_2") (pintype "passive"))
      (node (ref "R8") (pin "1") (pinfunction "1_1") (pintype "passive"))
      (node (ref "U8") (pin "10") (pinfunction "PA5/ADC12_IN5_10") (pintype "passive"))
    )
    (net (code "22") (name "/VOUT_2") (class "Default")
      (node (ref "CF3") (pin "1") (pinfunction "1_1") (pintype "passive"))
      (node (ref "CF4") (pin "1") (pinfunction "1_1") (pintype "passive"))
      (node (ref "R11") (pin "2") (pinfunction "2_2") (pintype "passive"))
      (node (ref "R9") (pin "1") (pinfunction "1_1") (pintype "passive"))
      (node (ref "U8") (pin "11") (pinfunction "PA6/ADC12_IN6_11") (pintype "passive"))
    )
    (net (code "23") (name "/VOUT_3") (class "Default")
      (node (ref "CF10") (pin "1") (pinfunction "1_1") (pintype "passive"))
      (node (ref "CF9") (pin "1") (pinfunction "1_1") (pintype "passive"))
      (node (ref "R21") (pin "1") (pinfunction "1_1") (pintype "passive"))
      (node (ref "R23") (pin "2") (pinfunction "2_2") (pintype "passive"))
      (node (ref "U8") (pin "12") (pinfunction "PA7/ADC_IN7_12") (pintype "passive"))
    )
    (net (code "24") (name "/VOUT_4") (class "Default")
      (node (ref "CF11") (pin "1") (pinfunction "1_1") (pintype "passive"))
      (node (ref "CF12") (pin "1") (pinfunction "1_1") (pintype "passive"))
      (node (ref "R22") (pin "1") (pinfunction "1_1") (pintype "passive"))
      (node (ref "R24") (pin "2") (pinfunction "2_2") (pintype "passive"))
      (node (ref "U8") (pin "13") (pinfunction "PB0/ADC12_IN8_13") (pintype "passive"))
    )
    (net (code "25") (name "/VOUT_5") (class "Default")
      (node (ref "CF17") (pin "1") (pinfunction "1_1") (pintype "passive"))
      (node (ref "CF18") (pin "1") (pinfunction "1_1") (pintype "passive"))
      (node (ref "R31") (pin "1") (pinfunction "1_1") (pintype "passive"))
      (node (ref "R32") (pin "2") (pinfunction "2_2") (pintype "passive"))
      (node (ref "U8") (pin "14") (pinfunction "PB1/ADC12_IN9_14") (pintype "passive"))
    )
    (net (code "26") (name "/Xa_1") (class "Default")
      (node (ref "R12") (pin "1") (pinfunction "1_1") (pintype "passive"))
      (node (ref "U8") (pin "18") (pinfunction "PB12_18") (pintype "passive"))
    )
    (net (code "27") (name "/Xa_2") (class "Default")
      (node (ref "R13") (pin "1") (pinfunction "1_1") (pintype "passive"))
      (node (ref "U8") (pin "20") (pinfunction "PB14_20") (pintype "passive"))
    )
    (net (code "28") (name "/Xa_3") (class "Default")
      (node (ref "R25") (pin "1") (pinfunction "1_1") (pintype "passive"))
      (node (ref "U8") (pin "22") (pinfunction "PA8_22") (pintype "passive"))
    )
    (net (code "29") (name "/Xa_4") (class "Default")
      (node (ref "R26") (pin "1") (pinfunction "1_1") (pintype "passive"))
      (node (ref "U8") (pin "26") (pinfunction "PA12/CAN_TX/USBDP_26") (pintype "passive"))
    )
    (net (code "30") (name "/Xa_5") (class "Default")
      (node (ref "R33") (pin "1") (pinfunction "1_1") (pintype "passive"))
      (node (ref "U8") (pin "31") (pinfunction "PB9_31") (pintype "passive"))
    )
    (net (code "31") (name "GND") (class "Default")
      (node (ref "C1") (pin "2") (pinfunction "2_2") (pintype "passive"))
      (node (ref "C10") (pin "2") (pinfunction "2_2") (pintype "passive"))
      (node (ref "C11") (pin "2") (pinfunction "2_2") (pintype "passive"))
      (node (ref "C12") (pin "2") (pinfunction "2_2") (pintype "passive"))
      (node (ref "C13") (pin "2") (pinfunction "2_2") (pintype "passive"))
      (node (ref "C14") (pin "2") (pinfunction "2_2") (pintype "passive"))
      (node (ref "C15") (pin "2") (pinfunction "2_2") (pintype "passive"))
      (node (ref "C16") (pin "2") (pinfunction "2_2") (pintype "passive"))
      (node (ref "C17") (pin "2") (pinfunction "2_2") (pintype "passive"))
      (node (ref "C18") (pin "2") (pinfunction "2_2") (pintype "passive"))
      (node (ref "C19") (pin "2") (pinfunction "2_2") (pintype "passive"))
      (node (ref "C2") (pin "2") (pinfunction "2_2") (pintype "passive"))
      (node (ref "C20") (pin "2") (pinfunction "2_2") (pintype "passive"))
      (node (ref "C21") (pin "2") (pinfunction "2_2") (pintype "passive"))
      (node (ref "C22") (pin "2") (pinfunction "2_2") (pintype "passive"))
      (node (ref "C23") (pin "2") (pinfunction "2_2") (pintype "passive"))
      (node (ref "C24") (pin "2") (pinfunction "2_2") (pintype "passive"))
      (node (ref "C25") (pin "2") (pinfunction "2_2") (pintype "passive"))
      (node (ref "C26") (pin "2") (pinfunction "2_2") (pintype "passive"))
      (node (ref "C3") (pin "2") (pinfunction "2_2") (pintype "passive"))
      (node (ref "C4") (pin "2") (pinfunction "2_2") (pintype "passive"))
      (node (ref "C5") (pin "2") (pinfunction "2_2") (pintype "passive"))
      (node (ref "C6") (pin "2") (pinfunction "2_2") (pintype "passive"))
      (node (ref "C7") (pin "2") (pinfunction "2_2") (pintype "passive"))
      (node (ref "C8") (pin "2") (pinfunction "2_2") (pintype "passive"))
      (node (ref "C9") (pin "2") (pinfunction "2_2") (pintype "passive"))
      (node (ref "CF1") (pin "2") (pinfunction "2_2") (pintype "passive"))
      (node (ref "CF10") (pin "2") (pinfunction "2_2") (pintype "passive"))
      (node (ref "CF11") (pin "2") (pinfunction "2_2") (pintype "passive"))
      (node (ref "CF12") (pin "2") (pinfunction "2_2") (pintype "passive"))
      (node (ref "CF13") (pin "2") (pinfunction "2_2") (pintype "passive"))
      (node (ref "CF14") (pin "2") (pinfunction "2_2") (pintype "passive"))
      (node (ref "CF15") (pin "2") (pinfunction "2_2") (pintype "passive"))
      (node (ref "CF16") (pin "2") (pinfunction "2_2") (pintype "passive"))
      (node (ref "CF17") (pin "2") (pinfunction "2_2") (pintype "passive"))
      (node (ref "CF18") (pin "2") (pinfunction "2_2") (pintype "passive"))
      (node (ref "CF19") (pin "2") (pinfunction "2_2") (pintype "passive"))
      (node (ref "CF2") (pin "2") (pinfunction "2_2") (pintype "passive"))
      (node (ref "CF20") (pin "2") (pinfunction "2_2") (pintype "passive"))
      (node (ref "CF3") (pin "2") (pinfunction "2_2") (pintype "passive"))
      (node (ref "CF4") (pin "2") (pinfunction "2_2") (pintype "passive"))
      (node (ref "CF5") (pin "2") (pinfunction "2_2") (pintype "passive"))
      (node (ref "CF6") (pin "2") (pinfunction "2_2") (pintype "passive"))
      (node (ref "CF7") (pin "2") (pinfunction "2_2") (pintype "passive"))
      (node (ref "CF8") (pin "2") (pinfunction "2_2") (pintype "passive"))
      (node (ref "CF9") (pin "2") (pinfunction "2_2") (pintype "passive"))
      (node (ref "D1") (pin "1") (pinfunction "A_1") (pintype "passive"))
      (node (ref "D2") (pin "1") (pinfunction "A_1") (pintype "passive"))
      (node (ref "D3") (pin "1") (pinfunction "A_1") (pintype "passive"))
      (node (ref "D4") (pin "1") (pinfunction "A_1") (pintype "passive"))
      (node (ref "D5") (pin "1") (pinfunction "A_1") (pintype "passive"))
      (node (ref "D6") (pin "1") (pinfunction "A_1") (pintype "passive"))
      (node (ref "D7") (pin "2") (pinfunction "K_2") (pintype "passive"))
      (node (ref "D8") (pin "2") (pinfunction "K_2") (pintype "passive"))
      (node (ref "J10") (pin "2") (pinfunction "2_2") (pintype "passive"))
      (node (ref "J12") (pin "2") (pinfunction "2_2") (pintype "passive"))
      (node (ref "J4") (pin "2") (pinfunction "2_2") (pintype "passive"))
      (node (ref "J5") (pin "2") (pinfunction "2_2") (pintype "passive"))
      (node (ref "J8") (pin "2") (pinfunction "2_2") (pintype "passive"))
      (node (ref "J9") (pin "2") (pinfunction "2_2") (pintype "passive"))
      (node (ref "LedFlick1") (pin "2") (pinfunction "K_2") (pintype "passive"))
      (node (ref "P1") (pin "1") (pinfunction "1_1") (pintype "passive"))
      (node (ref "P1") (pin "2") (pinfunction "2_2") (pintype "passive"))
      (node (ref "P1") (pin "3") (pinfunction "3_3") (pintype "passive"))
      (node (ref "P2") (pin "2") (pinfunction "2_2") (pintype "passive"))
      (node (ref "Q10") (pin "1") (pinfunction "E_1") (pintype "passive"))
      (node (ref "Q11") (pin "3") (pinfunction "B_3") (pintype "passive"))
      (node (ref "Q12") (pin "3") (pinfunction "B_3") (pintype "passive"))
      (node (ref "Q14") (pin "1") (pinfunction "E_1") (pintype "passive"))
      (node (ref "Q15") (pin "3") (pinfunction "B_3") (pintype "passive"))
      (node (ref "Q3") (pin "1") (pinfunction "E_1") (pintype "passive"))
      (node (ref "Q4") (pin "1") (pinfunction "E_1") (pintype "passive"))
      (node (ref "Q5") (pin "3") (pinfunction "B_3") (pintype "passive"))
      (node (ref "Q6") (pin "3") (pinfunction "B_3") (pintype "passive"))
      (node (ref "Q9") (pin "1") (pinfunction "E_1") (pintype "passive"))
      (node (ref "R10") (pin "1") (pinfunction "1_1") (pintype "passive"))
      (node (ref "R11") (pin "1") (pinfunction "1_1") (pintype "passive"))
      (node (ref "R16") (pin "1") (pinfunction "1_1") (pintype "passive"))
      (node (ref "R23") (pin "1") (pinfunction "1_1") (pintype "passive"))
      (node (ref "R24") (pin "1") (pinfunction "1_1") (pintype "passive"))
      (node (ref "R32") (pin "1") (pinfunction "1_1") (pintype "passive"))
      (node (ref "U1") (pin "3") (pinfunction "GND_3") (pintype "power_in"))
      (node (ref "U1") (pin "5") (pinfunction "~{ON}/OFF_5") (pintype "input"))
      (node (ref "U10") (pin "5") (pinfunction "GND_5") (pintype "passive"))
      (node (ref "U11") (pin "3") (pinfunction "GND_3") (pintype "power_in"))
      (node (ref "U11") (pin "5") (pinfunction "~{ON}/OFF_5") (pintype "input"))
      (node (ref "U12") (pin "1") (pinfunction "GND_1") (pintype "passive"))
      (node (ref "U13") (pin "3") (pinfunction "GND_3") (pintype "power_in"))
      (node (ref "U13") (pin "5") (pinfunction "~{ON}/OFF_5") (pintype "input"))
      (node (ref "U14") (pin "5") (pinfunction "GND_5") (pintype "passive"))
      (node (ref "U2") (pin "3") (pinfunction "GND_3") (pintype "power_in"))
      (node (ref "U2") (pin "5") (pinfunction "~{ON}/OFF_5") (pintype "input"))
      (node (ref "U3") (pin "5") (pinfunction "GND_5") (pintype "passive"))
      (node (ref "U4") (pin "5") (pinfunction "GND_5") (pintype "passive"))
      (node (ref "U5") (pin "5") (pinfunction "GND_5") (pintype "passive"))
      (node (ref "U6") (pin "3") (pinfunction "GND_3") (pintype "power_in"))
      (node (ref "U6") (pin "5") (pinfunction "~{ON}/OFF_5") (pintype "input"))
      (node (ref "U7") (pin "3") (pinfunction "GND_3") (pintype "power_in"))
      (node (ref "U7") (pin "5") (pinfunction "~{ON}/OFF_5") (pintype "input"))
      (node (ref "U8") (pin "33") (pinfunction "VSS1_33") (pintype "passive"))
      (node (ref "U8") (pin "34") (pinfunction "VSS2_34") (pintype "passive"))
      (node (ref "U9") (pin "5") (pinfunction "GND_5") (pintype "passive"))
      (node (ref "VR1") (pin "1") (pinfunction "TOP_1") (pintype "passive"))
      (node (ref "VR2") (pin "1") (pinfunction "TOP_1") (pintype "passive"))
      (node (ref "VR3") (pin "1") (pinfunction "TOP_1") (pintype "passive"))
      (node (ref "VR4") (pin "1") (pinfunction "TOP_1") (pintype "passive"))
      (node (ref "VR5") (pin "1") (pinfunction "TOP_1") (pintype "passive"))
    )
    (net (code "32") (name "Net-(D+_1-A)") (class "Default")
      (node (ref "D+_1") (pin "1") (pinfunction "A_1") (pintype "passive"))
      (node (ref "Q1") (pin "2") (pinfunction "E_2") (pintype "passive"))
    )
    (net (code "33") (name "Net-(D+_1-K)") (class "Default")
      (node (ref "D+_1") (pin "2") (pinfunction "K_2") (pintype "passive"))
      (node (ref "J2") (pin "2") (pinfunction "2_2") (pintype "passive"))
      (node (ref "U3") (pin "1") (pinfunction "IP+_1") (pintype "passive"))
      (node (ref "U3") (pin "2") (pinfunction "IP+_2") (pintype "passive"))
    )
    (net (code "34") (name "Net-(D+_2-A)") (class "Default")
      (node (ref "D+_2") (pin "1") (pinfunction "A_1") (pintype "passive"))
      (node (ref "Q2") (pin "2") (pinfunction "E_2") (pintype "passive"))
    )
    (net (code "35") (name "Net-(D+_2-K)") (class "Default")
      (node (ref "D+_2") (pin "2") (pinfunction "K_2") (pintype "passive"))
      (node (ref "J3") (pin "2") (pinfunction "2_2") (pintype "passive"))
      (node (ref "U4") (pin "1") (pinfunction "IP+_1") (pintype "passive"))
      (node (ref "U4") (pin "2") (pinfunction "IP+_2") (pintype "passive"))
    )
    (net (code "36") (name "Net-(D+_3-A)") (class "Default")
      (node (ref "D+_3") (pin "1") (pinfunction "A_1") (pintype "passive"))
      (node (ref "Q7") (pin "2") (pinfunction "E_2") (pintype "passive"))
    )
    (net (code "37") (name "Net-(D+_3-K)") (class "Default")
      (node (ref "D+_3") (pin "2") (pinfunction "K_2") (pintype "passive"))
      (node (ref "J6") (pin "2") (pinfunction "2_2") (pintype "passive"))
      (node (ref "U9") (pin "1") (pinfunction "IP+_1") (pintype "passive"))
      (node (ref "U9") (pin "2") (pinfunction "IP+_2") (pintype "passive"))
    )
    (net (code "38") (name "Net-(D+_4-A)") (class "Default")
      (node (ref "D+_4") (pin "1") (pinfunction "A_1") (pintype "passive"))
      (node (ref "Q8") (pin "2") (pinfunction "E_2") (pintype "passive"))
    )
    (net (code "39") (name "Net-(D+_4-K)") (class "Default")
      (node (ref "D+_4") (pin "2") (pinfunction "K_2") (pintype "passive"))
      (node (ref "J7") (pin "2") (pinfunction "2_2") (pintype "passive"))
      (node (ref "U10") (pin "1") (pinfunction "IP+_1") (pintype "passive"))
      (node (ref "U10") (pin "2") (pinfunction "IP+_2") (pintype "passive"))
    )
    (net (code "40") (name "Net-(D+_5-A)") (class "Default")
      (node (ref "D+_5") (pin "1") (pinfunction "A_1") (pintype "passive"))
      (node (ref "Q13") (pin "2") (pinfunction "E_2") (pintype "passive"))
    )
    (net (code "41") (name "Net-(D+_5-K)") (class "Default")
      (node (ref "D+_5") (pin "2") (pinfunction "K_2") (pintype "passive"))
      (node (ref "J11") (pin "2") (pinfunction "2_2") (pintype "passive"))
      (node (ref "U14") (pin "1") (pinfunction "IP+_1") (pintype "passive"))
      (node (ref "U14") (pin "2") (pinfunction "IP+_2") (pintype "passive"))
    )
    (net (code "42") (name "Net-(D1-K)") (class "Default")
      (node (ref "D1") (pin "2") (pinfunction "K_2") (pintype "passive"))
      (node (ref "L1") (pin "1") (pinfunction "1_1") (pintype "passive"))
      (node (ref "U1") (pin "2") (pinfunction "OUT_2") (pintype "power_in"))
    )
    (net (code "43") (name "Net-(D2-K)") (class "Default")
      (node (ref "D2") (pin "2") (pinfunction "K_2") (pintype "passive"))
      (node (ref "L2") (pin "1") (pinfunction "1_1") (pintype "passive"))
      (node (ref "U2") (pin "2") (pinfunction "OUT_2") (pintype "power_in"))
    )
    (net (code "44") (name "Net-(D3-K)") (class "Default")
      (node (ref "D3") (pin "2") (pinfunction "K_2") (pintype "passive"))
      (node (ref "L3") (pin "1") (pinfunction "1_1") (pintype "passive"))
      (node (ref "U6") (pin "2") (pinfunction "OUT_2") (pintype "power_in"))
    )
    (net (code "45") (name "Net-(D4-K)") (class "Default")
      (node (ref "D4") (pin "2") (pinfunction "K_2") (pintype "passive"))
      (node (ref "L4") (pin "1") (pinfunction "1_1") (pintype "passive"))
      (node (ref "U7") (pin "2") (pinfunction "OUT_2") (pintype "power_in"))
    )
    (net (code "46") (name "Net-(D5-K)") (class "Default")
      (node (ref "D5") (pin "2") (pinfunction "K_2") (pintype "passive"))
      (node (ref "L5") (pin "1") (pinfunction "1_1") (pintype "passive"))
      (node (ref "U11") (pin "2") (pinfunction "OUT_2") (pintype "power_in"))
    )
    (net (code "47") (name "Net-(D6-K)") (class "Default")
      (node (ref "D6") (pin "2") (pinfunction "K_2") (pintype "passive"))
      (node (ref "L6") (pin "1") (pinfunction "1_1") (pintype "passive"))
      (node (ref "U13") (pin "2") (pinfunction "OUT_2") (pintype "power_in"))
    )
    (net (code "48") (name "Net-(D7-A)") (class "Default")
      (node (ref "D7") (pin "1") (pinfunction "A_1") (pintype "passive"))
      (node (ref "R28") (pin "2") (pinfunction "2_2") (pintype "passive"))
    )
    (net (code "49") (name "Net-(D8-A)") (class "Default")
      (node (ref "D8") (pin "1") (pinfunction "A_1") (pintype "passive"))
      (node (ref "R29") (pin "2") (pinfunction "2_2") (pintype "passive"))
    )
    (net (code "50") (name "Net-(J4-Pad1)") (class "Default")
      (node (ref "J4") (pin "1") (pinfunction "1_1") (pintype "passive"))
      (node (ref "R8") (pin "2") (pinfunction "2_2") (pintype "passive"))
      (node (ref "U3") (pin "3") (pinfunction "IP-_3") (pintype "passive"))
      (node (ref "U3") (pin "4") (pinfunction "IP-_4") (pintype "passive"))
    )
    (net (code "51") (name "Net-(J5-Pad1)") (class "Default")
      (node (ref "J5") (pin "1") (pinfunction "1_1") (pintype "passive"))
      (node (ref "R9") (pin "2") (pinfunction "2_2") (pintype "passive"))
      (node (ref "U4") (pin "3") (pinfunction "IP-_3") (pintype "passive"))
      (node (ref "U4") (pin "4") (pinfunction "IP-_4") (pintype "passive"))
    )
    (net (code "52") (name "Net-(J8-Pad1)") (class "Default")
      (node (ref "J8") (pin "1") (pinfunction "1_1") (pintype "passive"))
      (node (ref "R21") (pin "2") (pinfunction "2_2") (pintype "passive"))
      (node (ref "U9") (pin "3") (pinfunction "IP-_3") (pintype "passive"))
      (node (ref "U9") (pin "4") (pinfunction "IP-_4") (pintype "passive"))
    )
    (net (code "53") (name "Net-(J9-Pad1)") (class "Default")
      (node (ref "J9") (pin "1") (pinfunction "1_1") (pintype "passive"))
      (node (ref "R22") (pin "2") (pinfunction "2_2") (pintype "passive"))
      (node (ref "U10") (pin "3") (pinfunction "IP-_3") (pintype "passive"))
      (node (ref "U10") (pin "4") (pinfunction "IP-_4") (pintype "passive"))
    )
    (net (code "54") (name "Net-(J12-Pad1)") (class "Default")
      (node (ref "J12") (pin "1") (pinfunction "1_1") (pintype "passive"))
      (node (ref "R31") (pin "2") (pinfunction "2_2") (pintype "passive"))
      (node (ref "U14") (pin "3") (pinfunction "IP-_3") (pintype "passive"))
      (node (ref "U14") (pin "4") (pinfunction "IP-_4") (pintype "passive"))
    )
    (net (code "55") (name "Net-(LedFlick1-A)") (class "Default")
      (node (ref "LedFlick1") (pin "1") (pinfunction "A_1") (pintype "passive"))
      (node (ref "R_LedFlick1") (pin "2") (pinfunction "2_2") (pintype "passive"))
    )
    (net (code "56") (name "Net-(Q1-B)") (class "Default")
      (node (ref "Q1") (pin "1") (pinfunction "B_1") (pintype "passive"))
      (node (ref "Q3") (pin "2") (pinfunction "C_2") (pintype "passive"))
      (node (ref "R4") (pin "2") (pinfunction "2_2") (pintype "passive"))
    )
    (net (code "57") (name "Net-(Q2-B)") (class "Default")
      (node (ref "Q2") (pin "1") (pinfunction "B_1") (pintype "passive"))
      (node (ref "Q4") (pin "2") (pinfunction "C_2") (pintype "passive"))
      (node (ref "R5") (pin "2") (pinfunction "2_2") (pintype "passive"))
    )
    (net (code "58") (name "Net-(Q3-B)") (class "Default")
      (node (ref "Q3") (pin "3") (pinfunction "B_3") (pintype "passive"))
      (node (ref "R6") (pin "2") (pinfunction "2_2") (pintype "passive"))
    )
    (net (code "59") (name "Net-(Q4-B)") (class "Default")
      (node (ref "Q4") (pin "3") (pinfunction "B_3") (pintype "passive"))
      (node (ref "R7") (pin "2") (pinfunction "2_2") (pintype "passive"))
    )
    (net (code "60") (name "Net-(Q5-C)") (class "Default")
      (node (ref "J2") (pin "1") (pinfunction "1_1") (pintype "passive"))
      (node (ref "Q5") (pin "2") (pinfunction "C_2") (pintype "passive"))
    )
    (net (code "61") (name "Net-(Q5-E)") (class "Default")
      (node (ref "Q5") (pin "1") (pinfunction "E_1") (pintype "passive"))
      (node (ref "R12") (pin "2") (pinfunction "2_2") (pintype "passive"))
    )
    (net (code "62") (name "Net-(Q6-C)") (class "Default")
      (node (ref "J3") (pin "1") (pinfunction "1_1") (pintype "passive"))
      (node (ref "Q6") (pin "2") (pinfunction "C_2") (pintype "passive"))
    )
    (net (code "63") (name "Net-(Q6-E)") (class "Default")
      (node (ref "Q6") (pin "1") (pinfunction "E_1") (pintype "passive"))
      (node (ref "R13") (pin "2") (pinfunction "2_2") (pintype "passive"))
    )
    (net (code "64") (name "Net-(Q7-B)") (class "Default")
      (node (ref "Q7") (pin "1") (pinfunction "B_1") (pintype "passive"))
      (node (ref "Q9") (pin "2") (pinfunction "C_2") (pintype "passive"))
      (node (ref "R17") (pin "2") (pinfunction "2_2") (pintype "passive"))
    )
    (net (code "65") (name "Net-(Q9-B)") (class "Default")
      (node (ref "Q9") (pin "3") (pinfunction "B_3") (pintype "passive"))
      (node (ref "R19") (pin "2") (pinfunction "2_2") (pintype "passive"))
    )
    (net (code "66") (name "Net-(Q10-B)") (class "Default")
      (node (ref "Q10") (pin "3") (pinfunction "B_3") (pintype "passive"))
      (node (ref "R20") (pin "2") (pinfunction "2_2") (pintype "passive"))
    )
    (net (code "67") (name "Net-(Q10-C)") (class "Default")
      (node (ref "Q10") (pin "2") (pinfunction "C_2") (pintype "passive"))
      (node (ref "Q8") (pin "1") (pinfunction "B_1") (pintype "passive"))
      (node (ref "R18") (pin "2") (pinfunction "2_2") (pintype "passive"))
    )
    (net (code "68") (name "Net-(Q11-C)") (class "Default")
      (node (ref "J6") (pin "1") (pinfunction "1_1") (pintype "passive"))
      (node (ref "Q11") (pin "2") (pinfunction "C_2") (pintype "passive"))
    )
    (net (code "69") (name "Net-(Q11-E)") (class "Default")
      (node (ref "Q11") (pin "1") (pinfunction "E_1") (pintype "passive"))
      (node (ref "R25") (pin "2") (pinfunction "2_2") (pintype "passive"))
    )
    (net (code "70") (name "Net-(Q12-C)") (class "Default")
      (node (ref "J7") (pin "1") (pinfunction "1_1") (pintype "passive"))
      (node (ref "Q12") (pin "2") (pinfunction "C_2") (pintype "passive"))
    )
    (net (code "71") (name "Net-(Q12-E)") (class "Default")
      (node (ref "Q12") (pin "1") (pinfunction "E_1") (pintype "passive"))
      (node (ref "R26") (pin "2") (pinfunction "2_2") (pintype "passive"))
    )
    (net (code "72") (name "Net-(Q13-B)") (class "Default")
      (node (ref "Q13") (pin "1") (pinfunction "B_1") (pintype "passive"))
      (node (ref "Q14") (pin "2") (pinfunction "C_2") (pintype "passive"))
      (node (ref "R27") (pin "2") (pinfunction "2_2") (pintype "passive"))
    )
    (net (code "73") (name "Net-(Q14-B)") (class "Default")
      (node (ref "Q14") (pin "3") (pinfunction "B_3") (pintype "passive"))
      (node (ref "R30") (pin "2") (pinfunction "2_2") (pintype "passive"))
    )
    (net (code "74") (name "Net-(Q15-C)") (class "Default")
      (node (ref "J11") (pin "1") (pinfunction "1_1") (pintype "passive"))
      (node (ref "Q15") (pin "2") (pinfunction "C_2") (pintype "passive"))
    )
    (net (code "75") (name "Net-(Q15-E)") (class "Default")
      (node (ref "Q15") (pin "1") (pinfunction "E_1") (pintype "passive"))
      (node (ref "R33") (pin "2") (pinfunction "2_2") (pintype "passive"))
    )
    (net (code "76") (name "Net-(U1-FB)") (class "Default")
      (node (ref "U1") (pin "4") (pinfunction "FB_4") (pintype "input"))
      (node (ref "VR1") (pin "2") (pinfunction "BOT_2") (pintype "passive"))
    )
    (net (code "77") (name "Net-(U2-FB)") (class "Default")
      (node (ref "U2") (pin "4") (pinfunction "FB_4") (pintype "input"))
      (node (ref "VR2") (pin "2") (pinfunction "BOT_2") (pintype "passive"))
    )
    (net (code "78") (name "Net-(U3-Filter)") (class "Default")
      (node (ref "C7") (pin "1") (pinfunction "1_1") (pintype "passive"))
      (node (ref "U3") (pin "6") (pinfunction "Filter_6") (pintype "passive"))
    )
    (net (code "79") (name "Net-(U4-Filter)") (class "Default")
      (node (ref "C8") (pin "1") (pinfunction "1_1") (pintype "passive"))
      (node (ref "U4") (pin "6") (pinfunction "Filter_6") (pintype "passive"))
    )
    (net (code "80") (name "Net-(U6-FB)") (class "Default")
      (node (ref "U6") (pin "4") (pinfunction "FB_4") (pintype "input"))
      (node (ref "VR3") (pin "2") (pinfunction "BOT_2") (pintype "passive"))
    )
    (net (code "81") (name "Net-(U7-FB)") (class "Default")
      (node (ref "U7") (pin "4") (pinfunction "FB_4") (pintype "input"))
      (node (ref "VR4") (pin "2") (pinfunction "BOT_2") (pintype "passive"))
    )
    (net (code "82") (name "Net-(U8-PB10{slash}USART3_TX{slash}I2C2_SCL)") (class "Default")
      (node (ref "R_LedFlick1") (pin "1") (pinfunction "1_1") (pintype "passive"))
      (node (ref "U8") (pin "16") (pinfunction "PB10/USART3_TX/I2C2_SCL_16") (pintype "passive"))
    )
    (net (code "83") (name "Net-(U9-Filter)") (class "Default")
      (node (ref "C15") (pin "1") (pinfunction "1_1") (pintype "passive"))
      (node (ref "U9") (pin "6") (pinfunction "Filter_6") (pintype "passive"))
    )
    (net (code "84") (name "Net-(U10-Filter)") (class "Default")
      (node (ref "C16") (pin "1") (pinfunction "1_1") (pintype "passive"))
      (node (ref "U10") (pin "6") (pinfunction "Filter_6") (pintype "passive"))
    )
    (net (code "85") (name "Net-(U11-FB)") (class "Default")
      (node (ref "U11") (pin "4") (pinfunction "FB_4") (pintype "input"))
      (node (ref "VR5") (pin "2") (pinfunction "BOT_2") (pintype "passive"))
    )
    (net (code "86") (name "Net-(U14-Filter)") (class "Default")
      (node (ref "C24") (pin "1") (pinfunction "1_1") (pintype "passive"))
      (node (ref "U14") (pin "6") (pinfunction "Filter_6") (pintype "passive"))
    )
    (net (code "87") (name "VCC-3V3") (class "Default")
      (node (ref "C25") (pin "1") (pinfunction "1_1") (pintype "passive"))
      (node (ref "C26") (pin "1") (pinfunction "1_1") (pintype "passive"))
      (node (ref "R1") (pin "2") (pinfunction "2_2") (pintype "passive"))
      (node (ref "R2") (pin "2") (pinfunction "2_2") (pintype "passive"))
      (node (ref "R28") (pin "1") (pinfunction "1_1") (pintype "passive"))
      (node (ref "R3") (pin "2") (pinfunction "2_2") (pintype "passive"))
      (node (ref "U12") (pin "2") (pinfunction "VOUT_2") (pintype "passive"))
      (node (ref "U8") (pin "35") (pinfunction "VDD1_35") (pintype "passive"))
      (node (ref "U8") (pin "36") (pinfunction "VDD2_36") (pintype "passive"))
    )
    (net (code "88") (name "VCC-5V") (class "Default")
      (node (ref "C13") (pin "1") (pinfunction "1_1") (pintype "passive"))
      (node (ref "C14") (pin "1") (pinfunction "1_1") (pintype "passive"))
      (node (ref "C21") (pin "1") (pinfunction "1_1") (pintype "passive"))
      (node (ref "C22") (pin "1") (pinfunction "1_1") (pintype "passive"))
      (node (ref "C23") (pin "1") (pinfunction "1_1") (pintype "passive"))
      (node (ref "C5") (pin "1") (pinfunction "1_1") (pintype "passive"))
      (node (ref "C6") (pin "1") (pinfunction "1_1") (pintype "passive"))
      (node (ref "L6") (pin "2") (pinfunction "2_2") (pintype "passive"))
      (node (ref "P2") (pin "1") (pinfunction "1_1") (pintype "passive"))
      (node (ref "R14") (pin "2") (pinfunction "2_2") (pintype "passive"))
      (node (ref "R29") (pin "1") (pinfunction "1_1") (pintype "passive"))
      (node (ref "U10") (pin "8") (pinfunction "VCC_8") (pintype "passive"))
      (node (ref "U12") (pin "3") (pinfunction "VIN_3") (pintype "passive"))
      (node (ref "U13") (pin "4") (pinfunction "FB_4") (pintype "input"))
      (node (ref "U14") (pin "8") (pinfunction "VCC_8") (pintype "passive"))
      (node (ref "U3") (pin "8") (pinfunction "VCC_8") (pintype "passive"))
      (node (ref "U4") (pin "8") (pinfunction "VCC_8") (pintype "passive"))
      (node (ref "U5") (pin "8") (pinfunction "VCC_8") (pintype "passive"))
      (node (ref "U9") (pin "8") (pinfunction "VCC_8") (pintype "passive"))
    )
    (net (code "89") (name "VCC-5V_1") (class "Default")
      (node (ref "C1") (pin "1") (pinfunction "1_1") (pintype "passive"))
      (node (ref "C2") (pin "1") (pinfunction "1_1") (pintype "passive"))
      (node (ref "L1") (pin "2") (pinfunction "2_2") (pintype "passive"))
      (node (ref "Q1") (pin "3") (pinfunction "C_3") (pintype "passive"))
      (node (ref "R4") (pin "1") (pinfunction "1_1") (pintype "passive"))
      (node (ref "VR1") (pin "3") (pinfunction "TAP_3") (pintype "passive"))
    )
    (net (code "90") (name "VCC-5V_2") (class "Default")
      (node (ref "C3") (pin "1") (pinfunction "1_1") (pintype "passive"))
      (node (ref "C4") (pin "1") (pinfunction "1_1") (pintype "passive"))
      (node (ref "L2") (pin "2") (pinfunction "2_2") (pintype "passive"))
      (node (ref "Q2") (pin "3") (pinfunction "C_3") (pintype "passive"))
      (node (ref "R5") (pin "1") (pinfunction "1_1") (pintype "passive"))
      (node (ref "VR2") (pin "3") (pinfunction "TAP_3") (pintype "passive"))
    )
    (net (code "91") (name "VCC-5V_3") (class "Default")
      (node (ref "C10") (pin "1") (pinfunction "1_1") (pintype "passive"))
      (node (ref "C9") (pin "1") (pinfunction "1_1") (pintype "passive"))
      (node (ref "L3") (pin "2") (pinfunction "2_2") (pintype "passive"))
      (node (ref "Q7") (pin "3") (pinfunction "C_3") (pintype "passive"))
      (node (ref "R17") (pin "1") (pinfunction "1_1") (pintype "passive"))
      (node (ref "VR3") (pin "3") (pinfunction "TAP_3") (pintype "passive"))
    )
    (net (code "92") (name "VCC-5V_4") (class "Default")
      (node (ref "C11") (pin "1") (pinfunction "1_1") (pintype "passive"))
      (node (ref "C12") (pin "1") (pinfunction "1_1") (pintype "passive"))
      (node (ref "L4") (pin "2") (pinfunction "2_2") (pintype "passive"))
      (node (ref "Q8") (pin "3") (pinfunction "C_3") (pintype "passive"))
      (node (ref "R18") (pin "1") (pinfunction "1_1") (pintype "passive"))
      (node (ref "VR4") (pin "3") (pinfunction "TAP_3") (pintype "passive"))
    )
    (net (code "93") (name "VCC-5V_5") (class "Default")
      (node (ref "C17") (pin "1") (pinfunction "1_1") (pintype "passive"))
      (node (ref "C18") (pin "1") (pinfunction "1_1") (pintype "passive"))
      (node (ref "L5") (pin "2") (pinfunction "2_2") (pintype "passive"))
      (node (ref "Q13") (pin "3") (pinfunction "C_3") (pintype "passive"))
      (node (ref "R27") (pin "1") (pinfunction "1_1") (pintype "passive"))
      (node (ref "VR5") (pin "3") (pinfunction "TAP_3") (pintype "passive"))
    )
    (net (code "94") (name "VCC-12V") (class "Default")
      (node (ref "C19") (pin "1") (pinfunction "1_1") (pintype "passive"))
      (node (ref "C20") (pin "1") (pinfunction "1_1") (pintype "passive"))
      (node (ref "J10") (pin "1") (pinfunction "1_1") (pintype "passive"))
      (node (ref "U1") (pin "1") (pinfunction "IN_1") (pintype "power_in"))
      (node (ref "U11") (pin "1") (pinfunction "IN_1") (pintype "power_in"))
      (node (ref "U13") (pin "1") (pinfunction "IN_1") (pintype "power_in"))
      (node (ref "U2") (pin "1") (pinfunction "IN_1") (pintype "power_in"))
      (node (ref "U6") (pin "1") (pinfunction "IN_1") (pintype "power_in"))
      (node (ref "U7") (pin "1") (pinfunction "IN_1") (pintype "power_in"))
    )
    (net (code "95") (name "unconnected-(U8-PB5{slash}I2C1_SMBAI-Pad27)") (class "Default")
      (node (ref "U8") (pin "27") (pinfunction "PB5/I2C1_SMBAI_27") (pintype "passive"))
    )
    (net (code "96") (name "unconnected-(U8-VBAT-Pad1)") (class "Default")
      (node (ref "U8") (pin "1") (pinfunction "VBAT_1") (pintype "passive"))
    )
  )
)
